# Power1.net
KiCad netlist of a schematic drawn in Altium Designer
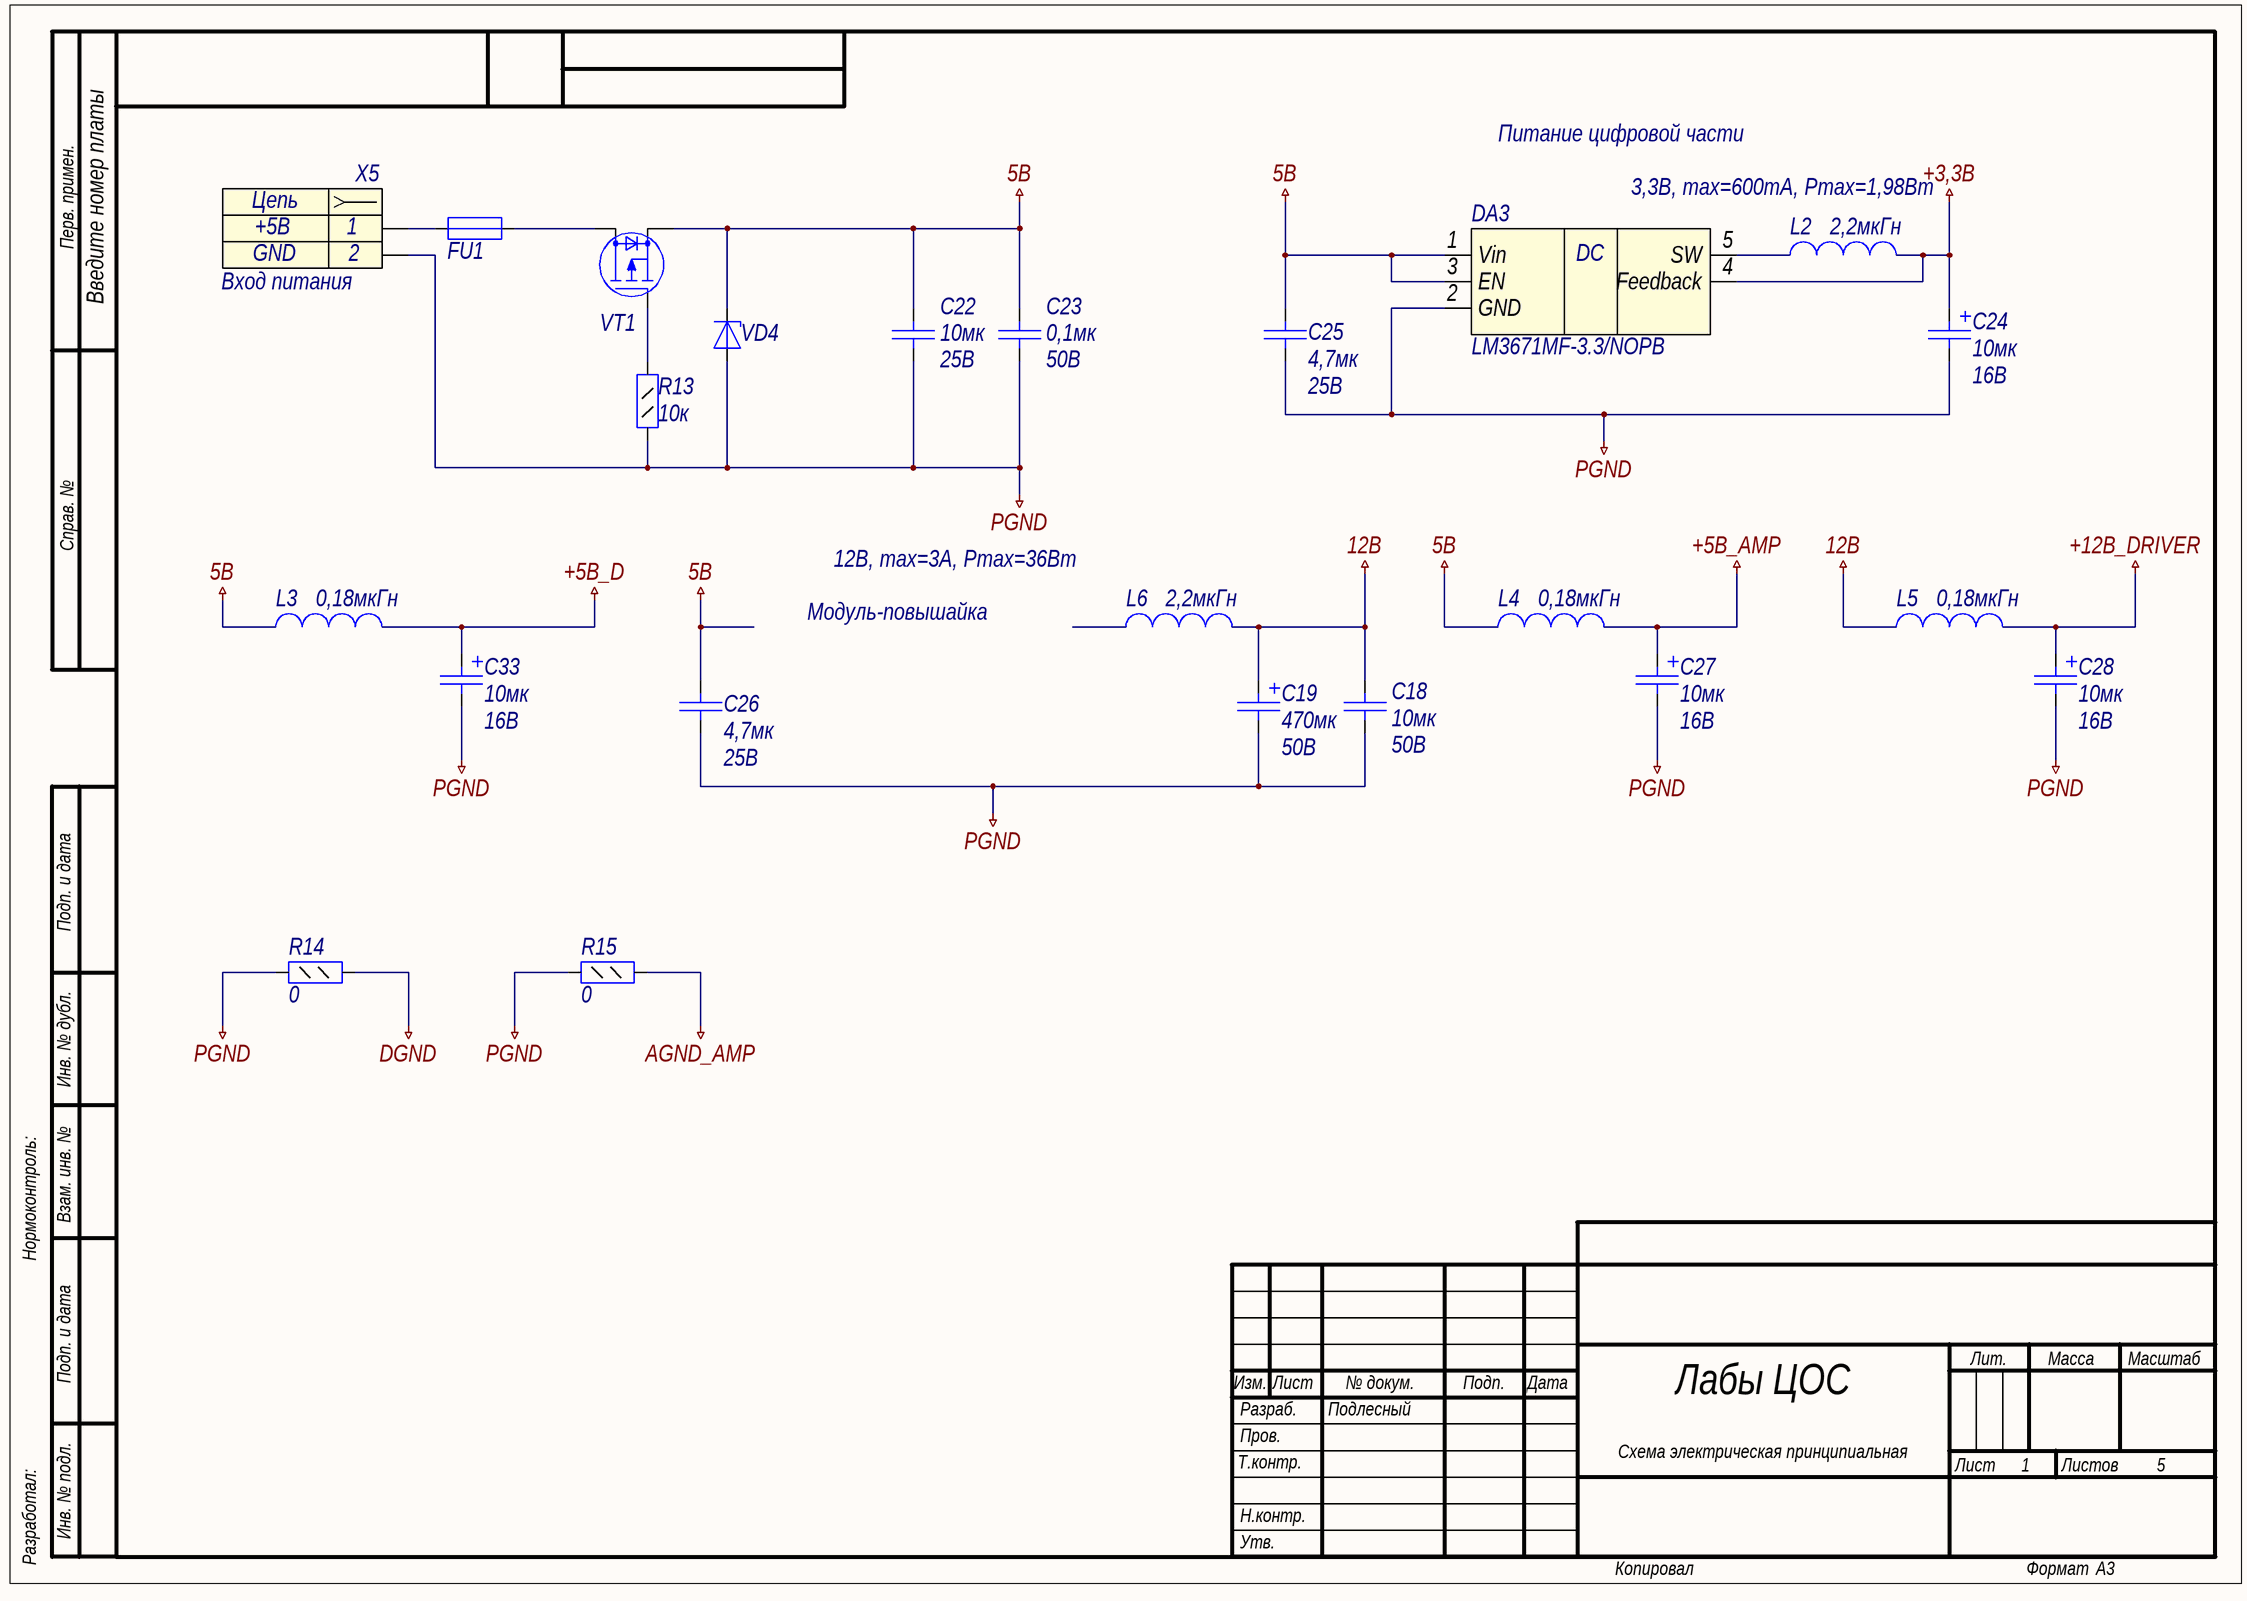
[diagram p0: Power1.SchDoc]

(export (version "E")
  (design (tool "Eeschema 10.0.6"))
  (components
    (comp (ref "C18")
      (value "10мк")
      (footprint "C1210")
      (description "Конденсатор")
      (fields
        (field (name "VOLTAGE") "50В")
        (field (name "PART NUMBER") "GRM32ER71H106K")
        (field (name "Comment") "Capacitor")
      )
      (libsource (lib "MOP44") (part "Capacitor"))
    )
    (comp (ref "C19")
      (value "470мк")
      (footprint "K50-35(10K20)_MIRROR")
      (description "Конденсатор полярный")
      (fields
        (field (name "VOLTAGE") "50В")
        (field (name "PART NUMBER") "TKR471M1HG20")
        (field (name "Comment") "Capacitor_pol")
      )
      (libsource (lib "MOP44") (part "Capacitor_pol"))
    )
    (comp (ref "C22")
      (value "10мк")
      (footprint "C1206")
      (description "Конденсатор")
      (fields
        (field (name "VOLTAGE") "25В")
        (field (name "PART NUMBER") "GRM31CR71E106KA12L*")
        (field (name "Comment") "Capacitor")
      )
      (libsource (lib "MOP44") (part "Capacitor"))
    )
    (comp (ref "C23")
      (value "0,1мк")
      (footprint "C0805")
      (description "Конденсатор")
      (fields
        (field (name "VOLTAGE") "50В")
        (field (name "PART NUMBER") "GRM21BR71H104KA01L ")
        (field (name "Comment") "Capacitor")
      )
      (libsource (lib "MOP44") (part "Capacitor"))
    )
    (comp (ref "C24")
      (value "10мк")
      (footprint "TANTAL CASE A")
      (description "Конденсатор полярный")
      (fields
        (field (name "VOLTAGE") "16В")
        (field (name "PART NUMBER") "293D106X9016A2TE3")
        (field (name "Comment") "Capacitor_pol")
      )
      (libsource (lib "MOP44") (part "Capacitor_pol"))
    )
    (comp (ref "C25")
      (value "4,7мк")
      (footprint "C0805")
      (description "Конденсатор")
      (fields
        (field (name "VOLTAGE") "25B")
        (field (name "PART NUMBER") "GRM21BR61E475KA12L")
        (field (name "Comment") "Capacitor")
      )
      (libsource (lib "MOP44") (part "Capacitor"))
    )
    (comp (ref "C26")
      (value "4,7мк")
      (footprint "C0805")
      (description "Конденсатор")
      (fields
        (field (name "VOLTAGE") "25B")
        (field (name "PART NUMBER") "GRM21BR61E475KA12L")
        (field (name "Comment") "Capacitor")
      )
      (libsource (lib "MOP44") (part "Capacitor"))
    )
    (comp (ref "C27")
      (value "10мк")
      (footprint "TANTAL CASE A")
      (description "Конденсатор полярный")
      (fields
        (field (name "VOLTAGE") "16В")
        (field (name "PART NUMBER") "293D106X9016A2TE3")
        (field (name "Comment") "Capacitor_pol")
      )
      (libsource (lib "MOP44") (part "Capacitor_pol"))
    )
    (comp (ref "C28")
      (value "10мк")
      (footprint "TANTAL CASE A")
      (description "Конденсатор полярный")
      (fields
        (field (name "VOLTAGE") "16В")
        (field (name "PART NUMBER") "293D106X9016A2TE3")
        (field (name "Comment") "Capacitor_pol")
      )
      (libsource (lib "MOP44") (part "Capacitor_pol"))
    )
    (comp (ref "C33")
      (value "10мк")
      (footprint "TANTAL CASE A")
      (description "Конденсатор полярный")
      (fields
        (field (name "VOLTAGE") "16В")
        (field (name "PART NUMBER") "293D106X9016A2TE3")
        (field (name "Comment") "Capacitor_pol")
      )
      (libsource (lib "MOP44") (part "Capacitor_pol"))
    )
    (comp (ref "DA3")
      (value "LM3671MF")
      (footprint "SOT23-5")
      (description "Step-Down DC-DC Converter")
      (fields
        (field (name "PART NUMBER") "LM3671MF-3.3/NOPB")
        (field (name "MANUFACTURER") "Texas Instruments")
      )
      (libsource (lib "MOP44") (part "LM3671MF"))
    )
    (comp (ref "FU1")
      (value "Fuse")
      (footprint "FUSE812")
      (description "Предохранитель")
      (fields (field (name "PART NUMBER") "MF-MSMF075"))
      (libsource (lib "MOP44") (part "Fuse"))
    )
    (comp (ref "L2")
      (value "2,2мкГн")
      (footprint "SDR0604")
      (description "EMI Suppression Filter")
      (fields (field (name "PART NUMBER") "SDR0604-2R2ML") (field (name "Comment") "Inductor"))
      (libsource (lib "MOP44") (part "Inductor"))
    )
    (comp (ref "L3")
      (value "0,18мкГн")
      (footprint "L0805")
      (description "EMI Suppression Filter")
      (fields (field (name "PART NUMBER") "CM201212-R18KL") (field (name "Comment") "Inductor"))
      (libsource (lib "MOP44") (part "Inductor"))
    )
    (comp (ref "L4")
      (value "0,18мкГн")
      (footprint "L0805")
      (description "EMI Suppression Filter")
      (fields (field (name "PART NUMBER") "CM201212-R18KL") (field (name "Comment") "Inductor"))
      (libsource (lib "MOP44") (part "Inductor"))
    )
    (comp (ref "L5")
      (value "0,18мкГн")
      (footprint "L0805")
      (description "EMI Suppression Filter")
      (fields (field (name "PART NUMBER") "CM201212-R18KL") (field (name "Comment") "Inductor"))
      (libsource (lib "MOP44") (part "Inductor"))
    )
    (comp (ref "L6")
      (value "2,2мкГн")
      (footprint "SDR0604")
      (description "EMI Suppression Filter")
      (fields (field (name "PART NUMBER") "SDR0604-2R2ML") (field (name "Comment") "Inductor"))
      (libsource (lib "MOP44") (part "Inductor"))
    )
    (comp (ref "R13")
      (value "10к")
      (footprint "R0805")
      (description "Резистор")
      (fields (field (name "PART NUMBER") "RC0805FR-0710KL") (field (name "POWER") "0,125Вт"))
      (libsource (lib "") (part "Resistor_0,125Вт_1"))
    )
    (comp (ref "R14")
      (value "0")
      (footprint "R0805")
      (description "Резистор")
      (fields (field (name "PART NUMBER") "RC0805FR-070RL") (field (name "POWER") "0,125Вт"))
      (libsource (lib "MOP44") (part "Resistor_0,125Вт"))
    )
    (comp (ref "R15")
      (value "0")
      (footprint "R0805")
      (description "Резистор")
      (fields (field (name "PART NUMBER") "RC0805FR-070RL") (field (name "POWER") "0,125Вт"))
      (libsource (lib "MOP44") (part "Resistor_0,125Вт"))
    )
    (comp (ref "VD4")
      (value "DiodeZener")
      (footprint "SMA")
      (description "Cтабилитрон (лавинный выпрямительный диод) односторонний")
      (fields (field (name "PART NUMBER") "SMAJ5.0A"))
      (libsource (lib "MOP44") (part "DiodeZener"))
    )
    (comp (ref "VT1")
      (value "P-MOSFET")
      (footprint "SOT23-3")
      (description "N-MOSFET")
      (fields
        (field (name "PART NUMBER") "IRLML6401TRPBF")
        (field (name "MANUFACTURER") "International Rectifier")
      )
      (libsource (lib "MOP44") (part "P-MOSFET"))
    )
    (comp (ref "X5")
      (value "Вход питания")
      (footprint "DS-210")
      (description "Разъем - 2 конт. розетка")
      (fields (field (name "PART NUMBER") "DS-210B(PBT)(NB)"))
      (libsource (lib "MOP44") (part "Header_2_sct"))
    )
  )
  (nets
    (net (code "1") (name "+3,3В") (class "Default")
      (node (ref "C24") (pin "1") (pinfunction "1_1") (pintype "passive"))
      (node (ref "DA3") (pin "4") (pinfunction "Feedback_4") (pintype "power_in"))
      (node (ref "L2") (pin "2") (pinfunction "2_2") (pintype "passive"))
    )
    (net (code "2") (name "+5B_D") (class "Default")
      (node (ref "C33") (pin "1") (pinfunction "1_1") (pintype "passive"))
      (node (ref "L3") (pin "2") (pinfunction "2_2") (pintype "passive"))
    )
    (net (code "3") (name "+5В_AMP") (class "Default")
      (node (ref "C27") (pin "1") (pinfunction "1_1") (pintype "passive"))
      (node (ref "L4") (pin "2") (pinfunction "2_2") (pintype "passive"))
    )
    (net (code "4") (name "+12В_DRIVER") (class "Default")
      (node (ref "C28") (pin "1") (pinfunction "1_1") (pintype "passive"))
      (node (ref "L5") (pin "2") (pinfunction "2_2") (pintype "passive"))
    )
    (net (code "5") (name "5B") (class "Default")
      (node (ref "C22") (pin "2") (pinfunction "2_2") (pintype "passive"))
      (node (ref "C23") (pin "2") (pinfunction "2_2") (pintype "passive"))
      (node (ref "C25") (pin "2") (pinfunction "2_2") (pintype "passive"))
      (node (ref "C26") (pin "2") (pinfunction "2_2") (pintype "passive"))
      (node (ref "DA3") (pin "1") (pinfunction "Vin_1") (pintype "power_in"))
      (node (ref "DA3") (pin "3") (pinfunction "EN_3") (pintype "power_in"))
      (node (ref "L3") (pin "1") (pinfunction "1_1") (pintype "passive"))
      (node (ref "L4") (pin "1") (pinfunction "1_1") (pintype "passive"))
      (node (ref "VD4") (pin "1") (pinfunction "K_1") (pintype "passive"))
      (node (ref "VT1") (pin "3") (pinfunction "S_3") (pintype "passive"))
    )
    (net (code "6") (name "12В") (class "Default")
      (node (ref "C18") (pin "2") (pinfunction "2_2") (pintype "passive"))
      (node (ref "C19") (pin "1") (pinfunction "1_1") (pintype "passive"))
      (node (ref "L5") (pin "1") (pinfunction "1_1") (pintype "passive"))
      (node (ref "L6") (pin "2") (pinfunction "2_2") (pintype "passive"))
    )
    (net (code "7") (name "AGND_AMP") (class "Default")
      (node (ref "R15") (pin "2") (pinfunction "2_2") (pintype "passive"))
    )
    (net (code "8") (name "DGND") (class "Default")
      (node (ref "R14") (pin "2") (pinfunction "2_2") (pintype "passive"))
    )
    (net (code "9") (name "Net-(DA3-SW)") (class "Default")
      (node (ref "DA3") (pin "5") (pinfunction "SW_5") (pintype "power_in"))
      (node (ref "L2") (pin "1") (pinfunction "1_1") (pintype "passive"))
    )
    (net (code "10") (name "Net-(FU1-Pad1)") (class "Default")
      (node (ref "FU1") (pin "1") (pinfunction "1_1") (pintype "passive"))
      (node (ref "X5") (pin "1") (pinfunction "1_1") (pintype "passive"))
    )
    (net (code "11") (name "Net-(VT1-D)") (class "Default")
      (node (ref "FU1") (pin "2") (pinfunction "2_2") (pintype "passive"))
      (node (ref "VT1") (pin "2") (pinfunction "D_2") (pintype "passive"))
    )
    (net (code "12") (name "Net-(VT1-G)") (class "Default")
      (node (ref "R13") (pin "2") (pinfunction "2_2") (pintype "passive"))
      (node (ref "VT1") (pin "1") (pinfunction "G_1") (pintype "passive"))
    )
    (net (code "13") (name "PGND") (class "Default")
      (node (ref "C18") (pin "1") (pinfunction "1_1") (pintype "passive"))
      (node (ref "C19") (pin "2") (pinfunction "2_2") (pintype "passive"))
      (node (ref "C22") (pin "1") (pinfunction "1_1") (pintype "passive"))
      (node (ref "C23") (pin "1") (pinfunction "1_1") (pintype "passive"))
      (node (ref "C24") (pin "2") (pinfunction "2_2") (pintype "passive"))
      (node (ref "C25") (pin "1") (pinfunction "1_1") (pintype "passive"))
      (node (ref "C26") (pin "1") (pinfunction "1_1") (pintype "passive"))
      (node (ref "C27") (pin "2") (pinfunction "2_2") (pintype "passive"))
      (node (ref "C28") (pin "2") (pinfunction "2_2") (pintype "passive"))
      (node (ref "C33") (pin "2") (pinfunction "2_2") (pintype "passive"))
      (node (ref "DA3") (pin "2") (pinfunction "GND_2") (pintype "power_in"))
      (node (ref "R13") (pin "1") (pinfunction "1_1") (pintype "passive"))
      (node (ref "R14") (pin "1") (pinfunction "1_1") (pintype "passive"))
      (node (ref "R15") (pin "1") (pinfunction "1_1") (pintype "passive"))
      (node (ref "VD4") (pin "2") (pinfunction "A_2") (pintype "passive"))
      (node (ref "X5") (pin "2") (pinfunction "2_2") (pintype "passive"))
    )
    (net (code "14") (name "unconnected-(L6-Pad1)") (class "Default")
      (node (ref "L6") (pin "1") (pinfunction "1_1") (pintype "passive"))
    )
  )
)
